# main.net
KiCad netlist of a schematic drawn in EAGLE
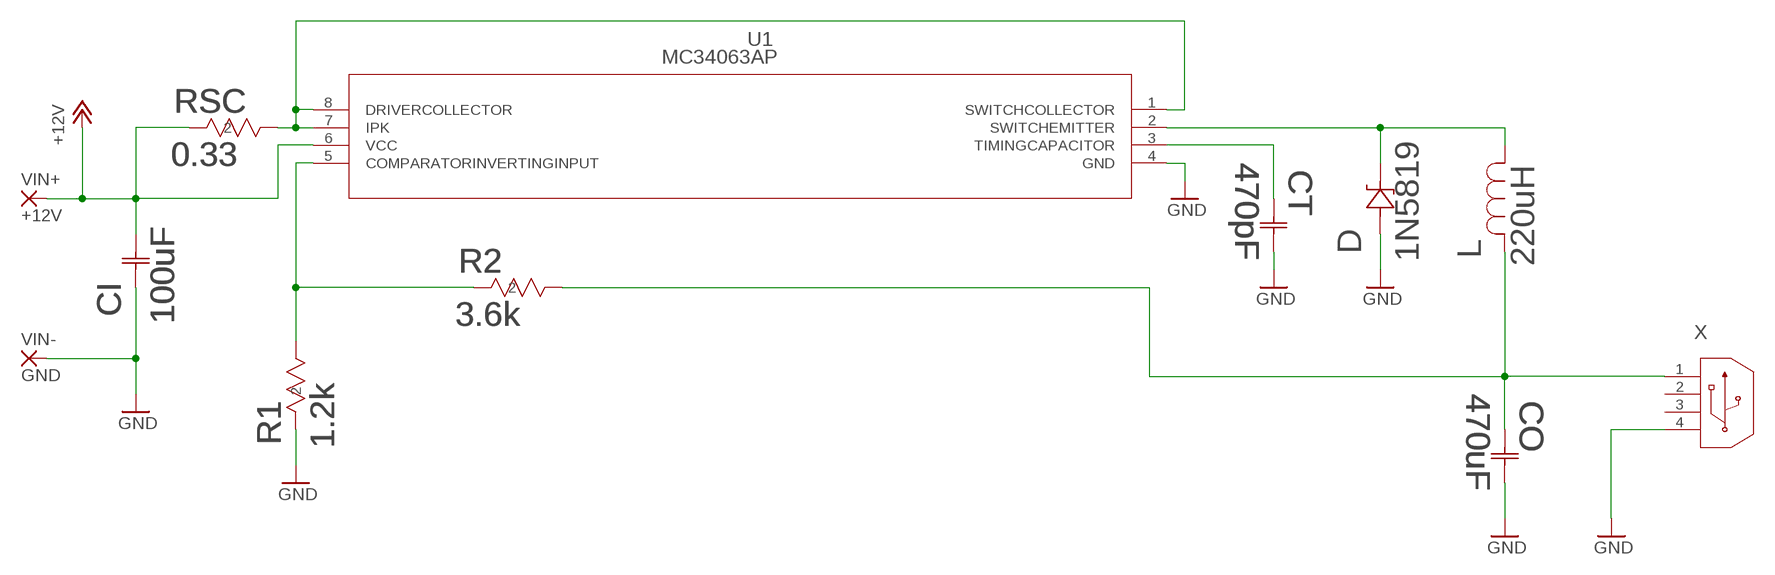
[diagram p0: schematic, sheet 1]

(export (version "E")
  (design (tool "Eeschema 10.0.6"))
  (components
    (comp (ref "CI")
      (value "100uF")
      (footprint "eagle-import:U1-I_NCH")
      (fields (field (name "MANUFACTURER_PART_NUMBER") "UVR1V101MED1TD"))
      (libsource (lib "eagle-import") (part "UVR1V101MED1TD"))
    )
    (comp (ref "CO")
      (value "470uF")
      (footprint "eagle-import:U1-I_NCH")
      (fields (field (name "MANUFACTURER_PART_NUMBER") "UVR1V101MED1TD"))
      (libsource (lib "eagle-import") (part "UVR1V101MED1TD"))
    )
    (comp (ref "CT")
      (value "470pF")
      (footprint "eagle-import:CAP_FA28_TDK")
      (fields
        (field (name "MANUFACTURER_PART_NUMBER") "FA28C0G1H471JNU06")
        (field (name "COPYRIGHT") "Copyright (C) 2018 Accelerated Designs. All rights reserved")
      )
      (libsource (lib "eagle-import") (part "FA28C0G1H471JNU06"))
    )
    (comp (ref "D")
      (value "1N5819")
      (footprint "eagle-import:DO-41_STM")
      (libsource (lib "eagle-import") (part "1N5819"))
    )
    (comp (ref "L")
      (value "220uH")
      (footprint "eagle-import:IND_6000")
      (fields (field (name "MANUFACTURER_PART_NUMBER") "6000-221K-RC"))
      (libsource (lib "eagle-import") (part "6000-221K-RC"))
    )
    (comp (ref "R1")
      (value "1.2k")
      (footprint "eagle-import:RES_MRS16_VIS")
      (fields (field (name "MANUFACTURER_PART_NUMBER") "MRS16000C1201FCT00"))
      (libsource (lib "eagle-import") (part "MRS16000C1201FCT00"))
    )
    (comp (ref "R2")
      (value "3.6k")
      (footprint "eagle-import:STA_RNMF14_STP")
      (fields (field (name "MANUFACTURER_PART_NUMBER") "RNMF14FTC3K60"))
      (libsource (lib "eagle-import") (part "RNMF14FTC3K60"))
    )
    (comp (ref "RSC")
      (value "0.33")
      (footprint "eagle-import:PF1262-0R33F1")
      (libsource (lib "eagle-import") (part "PF1262-0R33F1"))
    )
    (comp (ref "U1")
      (value "MC34063AP")
      (footprint "eagle-import:P8")
      (fields
        (field (name "GENERIC_PART_NUMBER") "MC34063A")
        (field (name "MANUFACTURER") "Texas Instruments")
      )
      (libsource (lib "eagle-import") (part "MC34063AP"))
    )
    (comp (ref "VIN+")
      (value "+12V")
      (footprint "eagle-import:2,54_1,1")
      (libsource (lib "eagle-import") (part "2,54/1,1"))
    )
    (comp (ref "VIN-")
      (value "GND")
      (footprint "eagle-import:2,54_1,1")
      (libsource (lib "eagle-import") (part "2,54/1,1"))
    )
    (comp (ref "X")
      (value "6364372-2")
      (footprint "eagle-import:CONN_6364372-2_TEC")
      (fields (field (name "COPYRIGHT") "Copyright (C) 2018 Accelerated Designs. All rights reserved"))
      (libsource (lib "eagle-import") (part "6364372-2"))
    )
  )
  (nets
    (net (code "1") (name "+12V") (class "Default")
      (node (ref "CI") (pin "2") (pinfunction "2_2") (pintype "passive"))
      (node (ref "RSC") (pin "2") (pinfunction "2_2") (pintype "passive"))
      (node (ref "U1") (pin "6") (pinfunction "VCC_6") (pintype "power_in"))
      (node (ref "VIN+") (pin "1") (pinfunction "P_1") (pintype "passive"))
    )
    (net (code "2") (name "GND") (class "Default")
      (node (ref "CI") (pin "1") (pinfunction "1_1") (pintype "passive"))
      (node (ref "CO") (pin "2") (pinfunction "2_2") (pintype "passive"))
      (node (ref "CT") (pin "2") (pinfunction "2_2") (pintype "passive"))
      (node (ref "D") (pin "2") (pinfunction "2_2") (pintype "passive"))
      (node (ref "R1") (pin "2") (pinfunction "2_2") (pintype "passive"))
      (node (ref "U1") (pin "4") (pinfunction "GND_4") (pintype "power_in"))
      (node (ref "VIN-") (pin "1") (pinfunction "P_1") (pintype "passive"))
      (node (ref "X") (pin "4") (pinfunction "4_4") (pintype "passive"))
    )
    (net (code "3") (name "Net-(CO-Pad1)") (class "Default")
      (node (ref "CO") (pin "1") (pinfunction "1_1") (pintype "passive"))
      (node (ref "L") (pin "2") (pinfunction "2_2") (pintype "passive"))
      (node (ref "R2") (pin "1") (pinfunction "1_1") (pintype "passive"))
      (node (ref "X") (pin "1") (pinfunction "1_1") (pintype "passive"))
    )
    (net (code "4") (name "Net-(U1-COMPARATORINVERTINGINPUT)") (class "Default")
      (node (ref "R1") (pin "1") (pinfunction "1_1") (pintype "passive"))
      (node (ref "R2") (pin "2") (pinfunction "2_2") (pintype "passive"))
      (node (ref "U1") (pin "5") (pinfunction "COMPARATORINVERTINGINPUT_5") (pintype "passive"))
    )
    (net (code "5") (name "Net-(U1-DRIVERCOLLECTOR)") (class "Default")
      (node (ref "RSC") (pin "1") (pinfunction "1_1") (pintype "passive"))
      (node (ref "U1") (pin "1") (pinfunction "SWITCHCOLLECTOR_1") (pintype "passive"))
      (node (ref "U1") (pin "7") (pinfunction "IPK_7") (pintype "passive"))
      (node (ref "U1") (pin "8") (pinfunction "DRIVERCOLLECTOR_8") (pintype "passive"))
    )
    (net (code "6") (name "Net-(U1-SWITCHEMITTER)") (class "Default")
      (node (ref "D") (pin "1") (pinfunction "1_1") (pintype "passive"))
      (node (ref "L") (pin "1") (pinfunction "1_1") (pintype "passive"))
      (node (ref "U1") (pin "2") (pinfunction "SWITCHEMITTER_2") (pintype "passive"))
    )
    (net (code "7") (name "Net-(U1-TIMINGCAPACITOR)") (class "Default")
      (node (ref "CT") (pin "1") (pinfunction "1_1") (pintype "passive"))
      (node (ref "U1") (pin "3") (pinfunction "TIMINGCAPACITOR_3") (pintype "passive"))
    )
    (net (code "8") (name "unconnected-(X-Pad2)") (class "Default")
      (node (ref "X") (pin "2") (pinfunction "2_2") (pintype "passive"))
    )
    (net (code "9") (name "unconnected-(X-Pad3)") (class "Default")
      (node (ref "X") (pin "3") (pinfunction "3_3") (pintype "passive"))
    )
  )
)
